# Connectores.net
KiCad netlist of a schematic drawn in Altium Designer
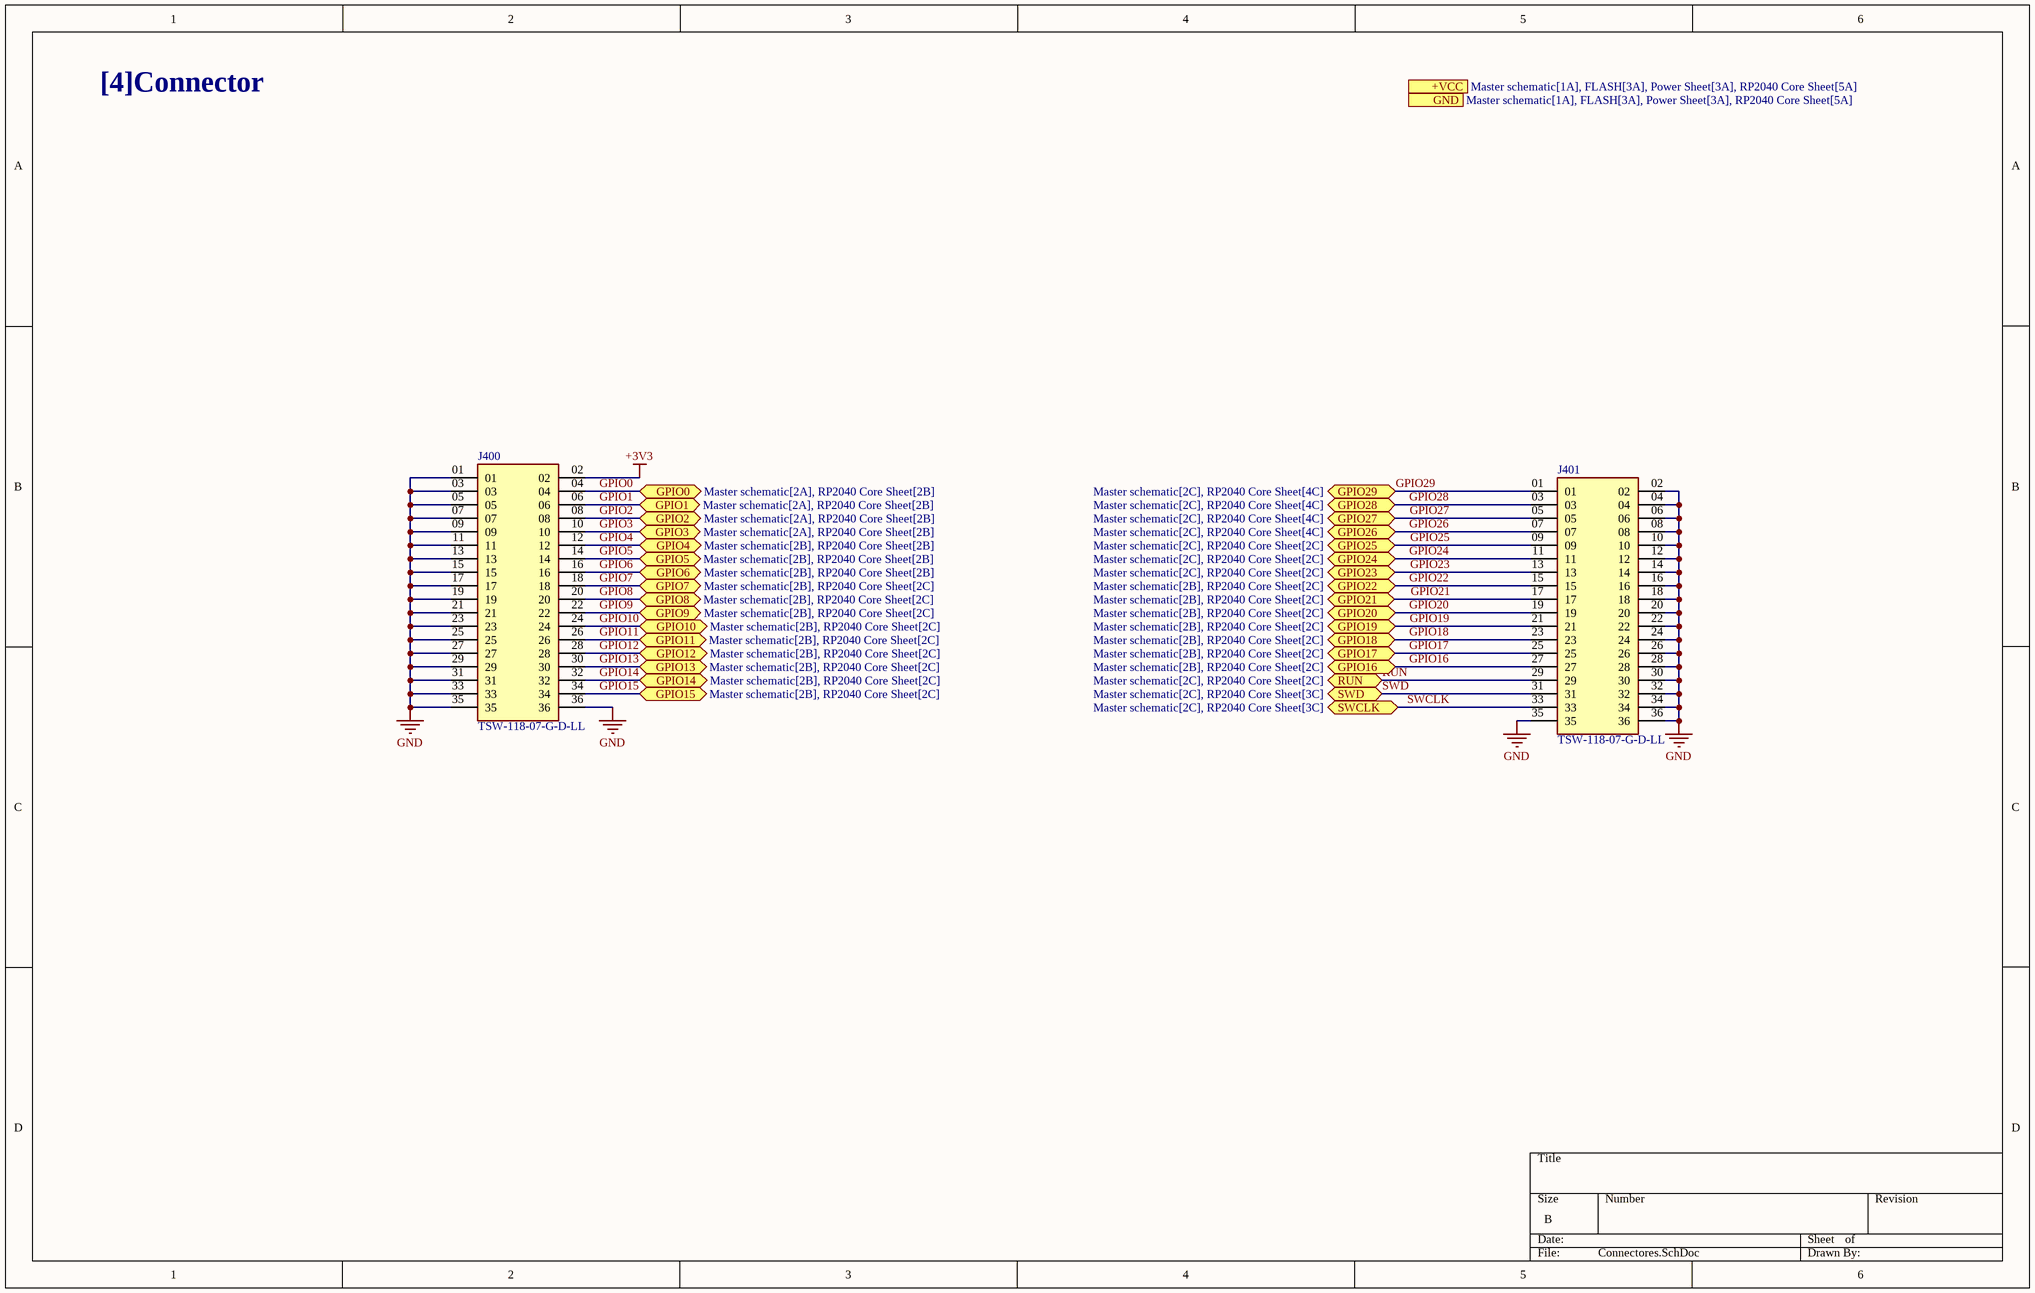
[diagram p0: Connectores.SchDoc]

(export (version "E")
  (design (tool "Eeschema 10.0.6"))
  (components
    (comp (ref "J400")
      (value "TSW-118-07-G-D-LL")
      (footprint "SAMTEC_TSW-118-07-G-D-LL")
      (libsource (lib "TSW-118-07-G-D-LL") (part "TSW-118-07-G-D-LL"))
    )
    (comp (ref "J401")
      (value "TSW-118-07-G-D-LL")
      (footprint "SAMTEC_TSW-118-07-G-D-LL")
      (libsource (lib "TSW-118-07-G-D-LL") (part "TSW-118-07-G-D-LL"))
    )
  )
  (nets
    (net (code "1") (name "+3V3") (class "Default")
      (node (ref "J400") (pin "02") (pinfunction "02_02") (pintype "passive"))
    )
    (net (code "3") (name "/GPIO0") (class "Default")
      (node (ref "J400") (pin "04") (pinfunction "04_04") (pintype "passive"))
    )
    (net (code "4") (name "/GPIO1") (class "Default")
      (node (ref "J400") (pin "06") (pinfunction "06_06") (pintype "passive"))
    )
    (net (code "5") (name "/GPIO2") (class "Default")
      (node (ref "J400") (pin "08") (pinfunction "08_08") (pintype "passive"))
    )
    (net (code "6") (name "/GPIO3") (class "Default")
      (node (ref "J400") (pin "10") (pinfunction "10_10") (pintype "passive"))
    )
    (net (code "7") (name "/GPIO4") (class "Default")
      (node (ref "J400") (pin "12") (pinfunction "12_12") (pintype "passive"))
    )
    (net (code "8") (name "/GPIO5") (class "Default")
      (node (ref "J400") (pin "14") (pinfunction "14_14") (pintype "passive"))
    )
    (net (code "9") (name "/GPIO6") (class "Default")
      (node (ref "J400") (pin "16") (pinfunction "16_16") (pintype "passive"))
    )
    (net (code "10") (name "/GPIO7") (class "Default")
      (node (ref "J400") (pin "18") (pinfunction "18_18") (pintype "passive"))
    )
    (net (code "11") (name "/GPIO8") (class "Default")
      (node (ref "J400") (pin "20") (pinfunction "20_20") (pintype "passive"))
    )
    (net (code "12") (name "/GPIO9") (class "Default")
      (node (ref "J400") (pin "22") (pinfunction "22_22") (pintype "passive"))
    )
    (net (code "13") (name "/GPIO10") (class "Default")
      (node (ref "J400") (pin "24") (pinfunction "24_24") (pintype "passive"))
    )
    (net (code "14") (name "/GPIO11") (class "Default")
      (node (ref "J400") (pin "26") (pinfunction "26_26") (pintype "passive"))
    )
    (net (code "15") (name "/GPIO12") (class "Default")
      (node (ref "J400") (pin "28") (pinfunction "28_28") (pintype "passive"))
    )
    (net (code "16") (name "/GPIO13") (class "Default")
      (node (ref "J400") (pin "30") (pinfunction "30_30") (pintype "passive"))
    )
    (net (code "17") (name "/GPIO14") (class "Default")
      (node (ref "J400") (pin "32") (pinfunction "32_32") (pintype "passive"))
    )
    (net (code "18") (name "/GPIO15") (class "Default")
      (node (ref "J400") (pin "34") (pinfunction "34_34") (pintype "passive"))
    )
    (net (code "19") (name "/GPIO16") (class "Default")
      (node (ref "J401") (pin "27") (pinfunction "27_27") (pintype "passive"))
    )
    (net (code "20") (name "/GPIO17") (class "Default")
      (node (ref "J401") (pin "25") (pinfunction "25_25") (pintype "passive"))
    )
    (net (code "21") (name "/GPIO18") (class "Default")
      (node (ref "J401") (pin "23") (pinfunction "23_23") (pintype "passive"))
    )
    (net (code "22") (name "/GPIO19") (class "Default")
      (node (ref "J401") (pin "21") (pinfunction "21_21") (pintype "passive"))
    )
    (net (code "23") (name "/GPIO20") (class "Default")
      (node (ref "J401") (pin "19") (pinfunction "19_19") (pintype "passive"))
    )
    (net (code "24") (name "/GPIO21") (class "Default")
      (node (ref "J401") (pin "17") (pinfunction "17_17") (pintype "passive"))
    )
    (net (code "25") (name "/GPIO22") (class "Default")
      (node (ref "J401") (pin "15") (pinfunction "15_15") (pintype "passive"))
    )
    (net (code "26") (name "/GPIO23") (class "Default")
      (node (ref "J401") (pin "13") (pinfunction "13_13") (pintype "passive"))
    )
    (net (code "27") (name "/GPIO24") (class "Default")
      (node (ref "J401") (pin "11") (pinfunction "11_11") (pintype "passive"))
    )
    (net (code "28") (name "/GPIO25") (class "Default")
      (node (ref "J401") (pin "09") (pinfunction "09_09") (pintype "passive"))
    )
    (net (code "29") (name "/GPIO26") (class "Default")
      (node (ref "J401") (pin "07") (pinfunction "07_07") (pintype "passive"))
    )
    (net (code "30") (name "/GPIO27") (class "Default")
      (node (ref "J401") (pin "05") (pinfunction "05_05") (pintype "passive"))
    )
    (net (code "31") (name "/GPIO28") (class "Default")
      (node (ref "J401") (pin "03") (pinfunction "03_03") (pintype "passive"))
    )
    (net (code "32") (name "/GPIO29") (class "Default")
      (node (ref "J401") (pin "01") (pinfunction "01_01") (pintype "passive"))
    )
    (net (code "33") (name "/RUN") (class "Default")
      (node (ref "J401") (pin "29") (pinfunction "29_29") (pintype "passive"))
    )
    (net (code "34") (name "/SWCLK") (class "Default")
      (node (ref "J401") (pin "33") (pinfunction "33_33") (pintype "passive"))
    )
    (net (code "35") (name "/SWD") (class "Default")
      (node (ref "J401") (pin "31") (pinfunction "31_31") (pintype "passive"))
    )
    (net (code "36") (name "GND") (class "Default")
      (node (ref "J400") (pin "01") (pinfunction "01_01") (pintype "passive"))
      (node (ref "J400") (pin "03") (pinfunction "03_03") (pintype "passive"))
      (node (ref "J400") (pin "05") (pinfunction "05_05") (pintype "passive"))
      (node (ref "J400") (pin "07") (pinfunction "07_07") (pintype "passive"))
      (node (ref "J400") (pin "09") (pinfunction "09_09") (pintype "passive"))
      (node (ref "J400") (pin "11") (pinfunction "11_11") (pintype "passive"))
      (node (ref "J400") (pin "13") (pinfunction "13_13") (pintype "passive"))
      (node (ref "J400") (pin "15") (pinfunction "15_15") (pintype "passive"))
      (node (ref "J400") (pin "17") (pinfunction "17_17") (pintype "passive"))
      (node (ref "J400") (pin "19") (pinfunction "19_19") (pintype "passive"))
      (node (ref "J400") (pin "21") (pinfunction "21_21") (pintype "passive"))
      (node (ref "J400") (pin "23") (pinfunction "23_23") (pintype "passive"))
      (node (ref "J400") (pin "25") (pinfunction "25_25") (pintype "passive"))
      (node (ref "J400") (pin "27") (pinfunction "27_27") (pintype "passive"))
      (node (ref "J400") (pin "29") (pinfunction "29_29") (pintype "passive"))
      (node (ref "J400") (pin "31") (pinfunction "31_31") (pintype "passive"))
      (node (ref "J400") (pin "33") (pinfunction "33_33") (pintype "passive"))
      (node (ref "J400") (pin "35") (pinfunction "35_35") (pintype "passive"))
      (node (ref "J400") (pin "36") (pinfunction "36_36") (pintype "passive"))
      (node (ref "J401") (pin "02") (pinfunction "02_02") (pintype "passive"))
      (node (ref "J401") (pin "04") (pinfunction "04_04") (pintype "passive"))
      (node (ref "J401") (pin "06") (pinfunction "06_06") (pintype "passive"))
      (node (ref "J401") (pin "08") (pinfunction "08_08") (pintype "passive"))
      (node (ref "J401") (pin "10") (pinfunction "10_10") (pintype "passive"))
      (node (ref "J401") (pin "12") (pinfunction "12_12") (pintype "passive"))
      (node (ref "J401") (pin "14") (pinfunction "14_14") (pintype "passive"))
      (node (ref "J401") (pin "16") (pinfunction "16_16") (pintype "passive"))
      (node (ref "J401") (pin "18") (pinfunction "18_18") (pintype "passive"))
      (node (ref "J401") (pin "20") (pinfunction "20_20") (pintype "passive"))
      (node (ref "J401") (pin "22") (pinfunction "22_22") (pintype "passive"))
      (node (ref "J401") (pin "24") (pinfunction "24_24") (pintype "passive"))
      (node (ref "J401") (pin "26") (pinfunction "26_26") (pintype "passive"))
      (node (ref "J401") (pin "28") (pinfunction "28_28") (pintype "passive"))
      (node (ref "J401") (pin "30") (pinfunction "30_30") (pintype "passive"))
      (node (ref "J401") (pin "32") (pinfunction "32_32") (pintype "passive"))
      (node (ref "J401") (pin "34") (pinfunction "34_34") (pintype "passive"))
      (node (ref "J401") (pin "35") (pinfunction "35_35") (pintype "passive"))
      (node (ref "J401") (pin "36") (pinfunction "36_36") (pintype "passive"))
    )
  )
)
